# Eagle_LED.net
KiCad netlist of a schematic drawn in EAGLE
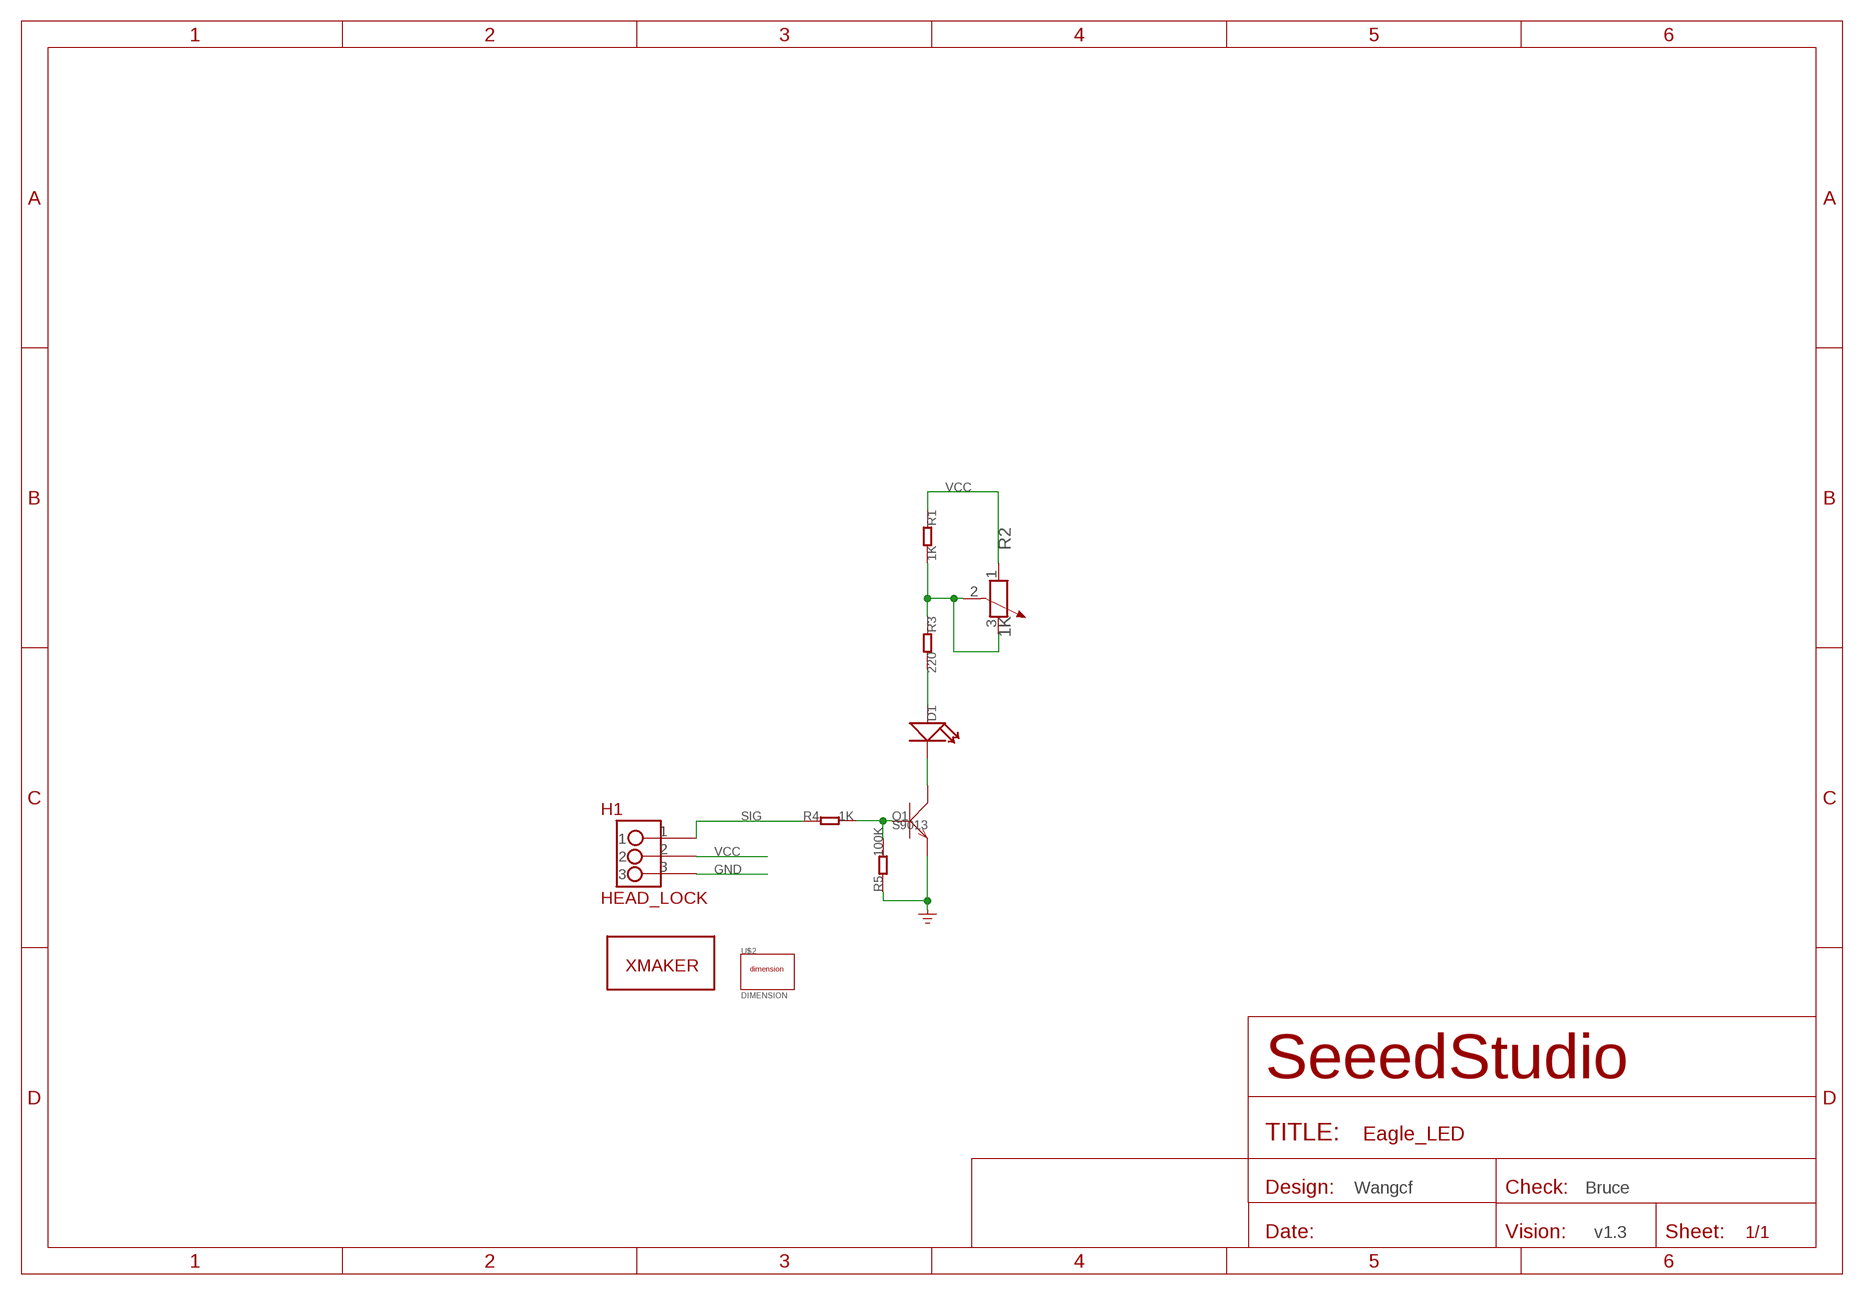
[diagram p0: schematic, sheet 1]

(export (version "E")
  (design (tool "Eeschema 10.0.6"))
  (components
    (comp (ref "D1")
      (value "LED-6MM")
      (footprint "eagle-import:LED-2P-2.54-6MM")
      (libsource (lib "eagle-import") (part "LED-6MM"))
    )
    (comp (ref "H1")
      (value "HEAD_LOCK")
      (footprint "eagle-import:HEAD_LOCK")
      (libsource (lib "eagle-import") (part "HEAD_LOCK"))
    )
    (comp (ref "Q1")
      (value "S9013")
      (footprint "eagle-import:SOT23")
      (libsource (lib "eagle-import") (part "TRANSISTOR-NPN-SOT23"))
    )
    (comp (ref "R1")
      (value "1K")
      (footprint "eagle-import:0603")
      (libsource (lib "eagle-import") (part "005-R0603"))
    )
    (comp (ref "R2")
      (value "1K")
      (footprint "eagle-import:3P-SQUA-6.7X6.4")
      (libsource (lib "eagle-import") (part "R-POTENTIOMETER'EVN-D8A-A03-B'"))
    )
    (comp (ref "R3")
      (value "220")
      (footprint "eagle-import:0603")
      (libsource (lib "eagle-import") (part "005-R0603"))
    )
    (comp (ref "R4")
      (value "1K")
      (footprint "eagle-import:0603")
      (libsource (lib "eagle-import") (part "005-R0603"))
    )
    (comp (ref "R5")
      (value "100K")
      (footprint "eagle-import:0603")
      (libsource (lib "eagle-import") (part "005-R0603"))
    )
    (comp (ref "U$2")
      (value "DIMENSION")
      (footprint "eagle-import:DIMENSION")
      (libsource (lib "eagle-import") (part "DIMENSION"))
    )
    (comp (ref "U$4")
      (value "XMAKERLOGO")
      (footprint "eagle-import:XMAKERLOGO")
      (libsource (lib "eagle-import") (part "XMAKERLOGO"))
    )
  )
  (nets
    (net (code "1") (name "/SIG") (class "Default")
      (node (ref "H1") (pin "1") (pinfunction "1_1") (pintype "passive"))
      (node (ref "R4") (pin "1") (pinfunction "1_1") (pintype "passive"))
    )
    (net (code "2") (name "/VCC") (class "Default")
      (node (ref "H1") (pin "2") (pinfunction "2_2") (pintype "passive"))
      (node (ref "R1") (pin "1") (pinfunction "1_1") (pintype "passive"))
      (node (ref "R2") (pin "1") (pinfunction "1_1") (pintype "passive"))
    )
    (net (code "3") (name "GND_POWER") (class "Default")
      (node (ref "H1") (pin "3") (pinfunction "3_3") (pintype "passive"))
      (node (ref "Q1") (pin "2") (pinfunction "E_2") (pintype "passive"))
      (node (ref "R5") (pin "1") (pinfunction "1_1") (pintype "passive"))
    )
    (net (code "4") (name "Net-(D1-Pad+)") (class "Default")
      (node (ref "D1") (pin "+") (pinfunction "+_+") (pintype "passive"))
      (node (ref "R3") (pin "2") (pinfunction "2_2") (pintype "passive"))
    )
    (net (code "5") (name "Net-(Q1-B)") (class "Default")
      (node (ref "Q1") (pin "1") (pinfunction "B_1") (pintype "passive"))
      (node (ref "R4") (pin "2") (pinfunction "2_2") (pintype "passive"))
      (node (ref "R5") (pin "2") (pinfunction "2_2") (pintype "passive"))
    )
    (net (code "6") (name "Net-(Q1-C)") (class "Default")
      (node (ref "D1") (pin "-") (pinfunction "-_-") (pintype "passive"))
      (node (ref "Q1") (pin "3") (pinfunction "C_3") (pintype "passive"))
    )
    (net (code "7") (name "Net-(R2-2)") (class "Default")
      (node (ref "R1") (pin "2") (pinfunction "2_2") (pintype "passive"))
      (node (ref "R2") (pin "2") (pinfunction "3_2") (pintype "passive"))
      (node (ref "R2") (pin "3") (pinfunction "2_3") (pintype "passive"))
      (node (ref "R3") (pin "1") (pinfunction "1_1") (pintype "passive"))
    )
  )
)
